# Sheet3.net
KiCad netlist of a schematic drawn in Altium Designer
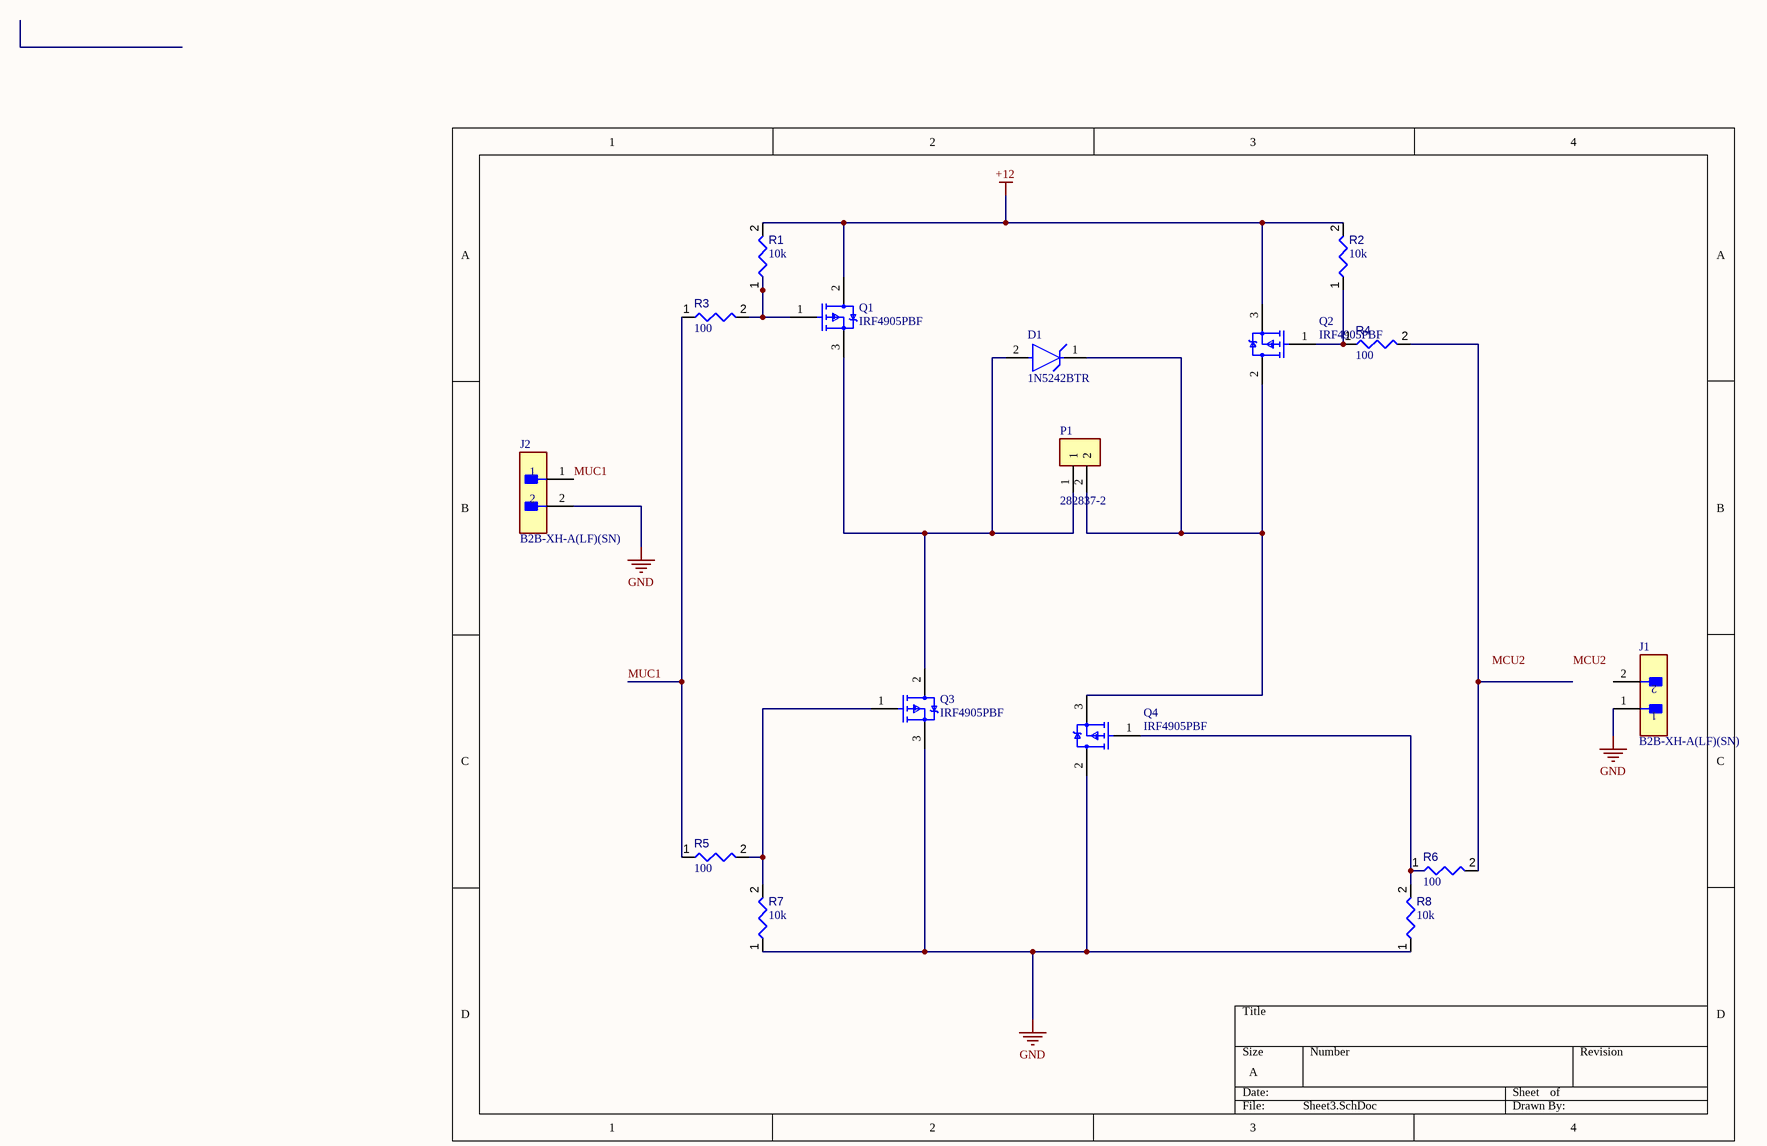
[diagram p0: Sheet3.SchDoc]

(export (version "E")
  (design (tool "Eeschema 10.0.6"))
  (components
    (comp (ref "D1")
      (value "1N5242BTR")
      (footprint "FP-017AG-MFG")
      (description "1N5242BTR 1N5242 Series 500 mW 12 V 200 mA Through Hole Zener Diode - DO-35")
      (fields (field (name "TOLERANCE") "5%"))
      (libsource (lib "Altium Content Vault") (part "f813f71cba58e380607f5dd3caf9714"))
    )
    (comp (ref "J1")
      (value "B2B-XH-A(LF)(SN)")
      (footprint "FP-B2B-XH-A_LF_SN-MFG")
      (description "CONN HEADER VERT 2POS 2.5MM")
      (libsource (lib "") (part "3bc925449376181038e59eaffc5286c_1"))
    )
    (comp (ref "J2")
      (value "B2B-XH-A(LF)(SN)")
      (footprint "FP-B2B-XH-A_LF_SN-MFG")
      (description "CONN HEADER VERT 2POS 2.5MM")
      (libsource (lib "Altium Content Vault") (part "3bc925449376181038e59eaffc5286c"))
    )
    (comp (ref "P1")
      (value "282837-2")
      (footprint "TE_282837-2")
      (fields (field (name "MF") "TE Connectivity"))
      (libsource (lib "282837-2") (part "282837-2"))
    )
    (comp (ref "Q1")
      (value "IRF4905PBF")
      (footprint "FP-PG-TO220-3-MFG")
      (description "MOSFET P-CH 55V 74A TO-220AB")
      (libsource (lib "Altium Content Vault") (part "7c43f5ccbd0f8ca8bbf61673af0f16f"))
    )
    (comp (ref "Q2")
      (value "IRF4905PBF")
      (footprint "FP-PG-TO220-3-MFG")
      (description "MOSFET P-CH 55V 74A TO-220AB")
      (libsource (lib "Altium Content Vault") (part "7c43f5ccbd0f8ca8bbf61673af0f16f"))
    )
    (comp (ref "Q3")
      (value "IRF4905PBF")
      (footprint "FP-PG-TO220-3-MFG")
      (description "MOSFET P-CH 55V 74A TO-220AB")
      (libsource (lib "Altium Content Vault") (part "7c43f5ccbd0f8ca8bbf61673af0f16f"))
    )
    (comp (ref "Q4")
      (value "IRF4905PBF")
      (footprint "FP-PG-TO220-3-MFG")
      (description "MOSFET P-CH 55V 74A TO-220AB")
      (libsource (lib "Altium Content Vault") (part "7c43f5ccbd0f8ca8bbf61673af0f16f"))
    )
    (comp (ref "R1")
      (value "10k")
      (footprint "RESC2013X50X35ML15T15")
      (description "Chip Resistor, 10 KOhm, +/- 1%, 125 mW, -55 to 155 degC, 0805 (2012 Metric)")
      (fields (field (name "TOLERANCE") "1%") (field (name "POWER") "125mW"))
      (libsource (lib "Nour Yossef") (part "RES-2"))
    )
    (comp (ref "R2")
      (value "10k")
      (footprint "RESC2013X50X35ML15T15")
      (description "Chip Resistor, 10 KOhm, +/- 1%, 125 mW, -55 to 155 degC, 0805 (2012 Metric)")
      (fields (field (name "TOLERANCE") "1%") (field (name "POWER") "125mW"))
      (libsource (lib "Nour Yossef") (part "RES-2"))
    )
    (comp (ref "R3")
      (value "100")
      (footprint "RESC0402(1005)_L")
      (description "Chip Resistor, 100 Ohms, +/-1 %, 63 mW, -55 to 155 degC, 0402")
      (fields (field (name "POWER") "63mW") (field (name "TOLERANCE") "1%"))
      (libsource (lib "Nour Yossef") (part "RES-2"))
    )
    (comp (ref "R4")
      (value "100")
      (footprint "RESC0402(1005)_L")
      (description "Chip Resistor, 100 Ohms, +/-1 %, 63 mW, -55 to 155 degC, 0402")
      (fields (field (name "POWER") "63mW") (field (name "TOLERANCE") "1%"))
      (libsource (lib "Nour Yossef") (part "RES-2"))
    )
    (comp (ref "R5")
      (value "100")
      (footprint "RESC0402(1005)_L")
      (description "Chip Resistor, 100 Ohms, +/-1 %, 63 mW, -55 to 155 degC, 0402")
      (fields (field (name "POWER") "63mW") (field (name "TOLERANCE") "1%"))
      (libsource (lib "Nour Yossef") (part "RES-2"))
    )
    (comp (ref "R6")
      (value "100")
      (footprint "RESC0402(1005)_L")
      (description "Chip Resistor, 100 Ohms, +/-1 %, 63 mW, -55 to 155 degC, 0402")
      (fields (field (name "POWER") "63mW") (field (name "TOLERANCE") "1%"))
      (libsource (lib "Nour Yossef") (part "RES-2"))
    )
    (comp (ref "R7")
      (value "10k")
      (footprint "RESC2013X50X35ML15T15")
      (description "Chip Resistor, 10 KOhm, +/- 1%, 125 mW, -55 to 155 degC, 0805 (2012 Metric)")
      (fields (field (name "TOLERANCE") "1%") (field (name "POWER") "125mW"))
      (libsource (lib "Nour Yossef") (part "RES-2"))
    )
    (comp (ref "R8")
      (value "10k")
      (footprint "RESC2013X50X35ML15T15")
      (description "Chip Resistor, 10 KOhm, +/- 1%, 125 mW, -55 to 155 degC, 0805 (2012 Metric)")
      (fields (field (name "TOLERANCE") "1%") (field (name "POWER") "125mW"))
      (libsource (lib "Nour Yossef") (part "RES-2"))
    )
  )
  (nets
    (net (code "1") (name "+12") (class "Default")
      (node (ref "Q1") (pin "2") (pinfunction "DRAIN_2") (pintype "passive"))
      (node (ref "Q2") (pin "3") (pinfunction "SOURCE_3") (pintype "passive"))
      (node (ref "R1") (pin "2") (pinfunction "2_2") (pintype "passive"))
      (node (ref "R2") (pin "2") (pinfunction "2_2") (pintype "passive"))
    )
    (net (code "3") (name "/MUC1") (class "Default")
      (node (ref "J2") (pin "1") (pinfunction "1_1") (pintype "passive"))
      (node (ref "R3") (pin "1") (pinfunction "1_1") (pintype "passive"))
      (node (ref "R5") (pin "1") (pinfunction "1_1") (pintype "passive"))
    )
    (net (code "4") (name "GND") (class "Default")
      (node (ref "J1") (pin "1") (pinfunction "1_1") (pintype "passive"))
      (node (ref "J2") (pin "2") (pinfunction "2_2") (pintype "passive"))
      (node (ref "Q3") (pin "3") (pinfunction "SOURCE_3") (pintype "passive"))
      (node (ref "Q4") (pin "2") (pinfunction "DRAIN_2") (pintype "passive"))
      (node (ref "R7") (pin "1") (pinfunction "1_1") (pintype "passive"))
      (node (ref "R8") (pin "1") (pinfunction "1_1") (pintype "passive"))
    )
    (net (code "5") (name "Net-(D1-A)") (class "Default")
      (node (ref "D1") (pin "2") (pinfunction "A_2") (pintype "passive"))
      (node (ref "P1") (pin "1") (pinfunction "1_1") (pintype "passive"))
      (node (ref "Q1") (pin "3") (pinfunction "SOURCE_3") (pintype "passive"))
      (node (ref "Q3") (pin "2") (pinfunction "DRAIN_2") (pintype "passive"))
    )
    (net (code "6") (name "Net-(D1-C)") (class "Default")
      (node (ref "D1") (pin "1") (pinfunction "C_1") (pintype "passive"))
      (node (ref "P1") (pin "2") (pinfunction "2_2") (pintype "passive"))
      (node (ref "Q2") (pin "2") (pinfunction "DRAIN_2") (pintype "passive"))
      (node (ref "Q4") (pin "3") (pinfunction "SOURCE_3") (pintype "passive"))
    )
    (net (code "7") (name "Net-(Q1-GATE)") (class "Default")
      (node (ref "Q1") (pin "1") (pinfunction "GATE_1") (pintype "passive"))
      (node (ref "R1") (pin "1") (pinfunction "1_1") (pintype "passive"))
      (node (ref "R3") (pin "2") (pinfunction "2_2") (pintype "passive"))
    )
    (net (code "8") (name "Net-(Q2-GATE)") (class "Default")
      (node (ref "Q2") (pin "1") (pinfunction "GATE_1") (pintype "passive"))
      (node (ref "R2") (pin "1") (pinfunction "1_1") (pintype "passive"))
      (node (ref "R4") (pin "1") (pinfunction "1_1") (pintype "passive"))
    )
    (net (code "9") (name "Net-(Q3-GATE)") (class "Default")
      (node (ref "Q3") (pin "1") (pinfunction "GATE_1") (pintype "passive"))
      (node (ref "R5") (pin "2") (pinfunction "2_2") (pintype "passive"))
      (node (ref "R7") (pin "2") (pinfunction "2_2") (pintype "passive"))
    )
    (net (code "10") (name "Net-(Q4-GATE)") (class "Default")
      (node (ref "Q4") (pin "1") (pinfunction "GATE_1") (pintype "passive"))
      (node (ref "R6") (pin "1") (pinfunction "1_1") (pintype "passive"))
      (node (ref "R8") (pin "2") (pinfunction "2_2") (pintype "passive"))
    )
    (net (code "11") (name "Net-(R4-Pad2)") (class "Default")
      (node (ref "R4") (pin "2") (pinfunction "2_2") (pintype "passive"))
      (node (ref "R6") (pin "2") (pinfunction "2_2") (pintype "passive"))
    )
    (net (code "12") (name "unconnected-(J1-Pad2)") (class "Default")
      (node (ref "J1") (pin "2") (pinfunction "2_2") (pintype "passive"))
    )
  )
)
